# Smarty-PPG-Module.net
KiCad netlist of a schematic drawn in EAGLE
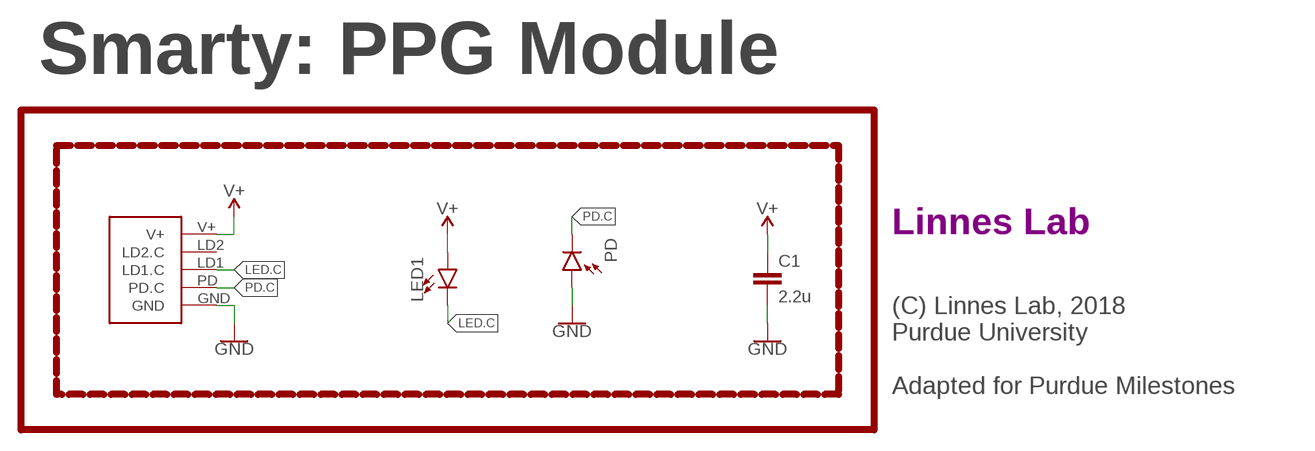
[diagram p0: schematic, sheet 1]

(export (version "E")
  (design (tool "Eeschema 10.0.6"))
  (components
    (comp (ref "C1")
      (value "2.2u")
      (footprint "eagle-import:C0603")
      (libsource (lib "eagle-import") (part "CAPACITOR0603"))
    )
    (comp (ref "J1")
      (value "PPG.MODULE.2")
      (footprint "eagle-import:PPG.MODULE.2")
      (libsource (lib "eagle-import") (part "PPG.MODULE.2"))
    )
    (comp (ref "LED1")
      (value "LED0805")
      (footprint "eagle-import:LED-0805")
      (libsource (lib "eagle-import") (part "LED0805"))
    )
    (comp (ref "PD")
      (value "PHOTODIODE.-SMD.GULLWING")
      (footprint "eagle-import:2-SMD.GULLWING")
      (libsource (lib "eagle-import") (part "PHOTODIODE.-SMD.GULLWING"))
    )
    (comp (ref "U$3")
      (value "LINNES.LAB.LOGO")
      (footprint "eagle-import:LINNES.LAB.LOGO")
      (libsource (lib "eagle-import") (part "LINNES.LAB.LOGO"))
    )
  )
  (nets
    (net (code "1") (name "GND") (class "Default")
      (node (ref "C1") (pin "2") (pinfunction "2_2") (pintype "passive"))
      (node (ref "J1") (pin "GND") (pinfunction "GND_GND") (pintype "bidirectional"))
      (node (ref "PD") (pin "+") (pinfunction "A_+") (pintype "passive"))
    )
    (net (code "2") (name "LED.C") (class "Default")
      (node (ref "J1") (pin "LD1") (pinfunction "LD1.C_LD1") (pintype "bidirectional"))
      (node (ref "LED1") (pin "C") (pinfunction "C_C") (pintype "passive"))
    )
    (net (code "3") (name "PD.C") (class "Default")
      (node (ref "J1") (pin "PD") (pinfunction "PD.C_PD") (pintype "bidirectional"))
      (node (ref "PD") (pin "-") (pinfunction "C_-") (pintype "passive"))
    )
    (net (code "4") (name "V+") (class "Default")
      (node (ref "C1") (pin "1") (pinfunction "1_1") (pintype "passive"))
      (node (ref "J1") (pin "V+") (pinfunction "V+_V+") (pintype "bidirectional"))
      (node (ref "LED1") (pin "A") (pinfunction "A_A") (pintype "passive"))
    )
    (net (code "5") (name "unconnected-(J1-LD2.C-PadLD2)") (class "Default")
      (node (ref "J1") (pin "LD2") (pinfunction "LD2.C_LD2") (pintype "bidirectional"))
    )
  )
)
